# BEE_BOARD_TOP.net
KiCad netlist of a schematic drawn in Altium Designer
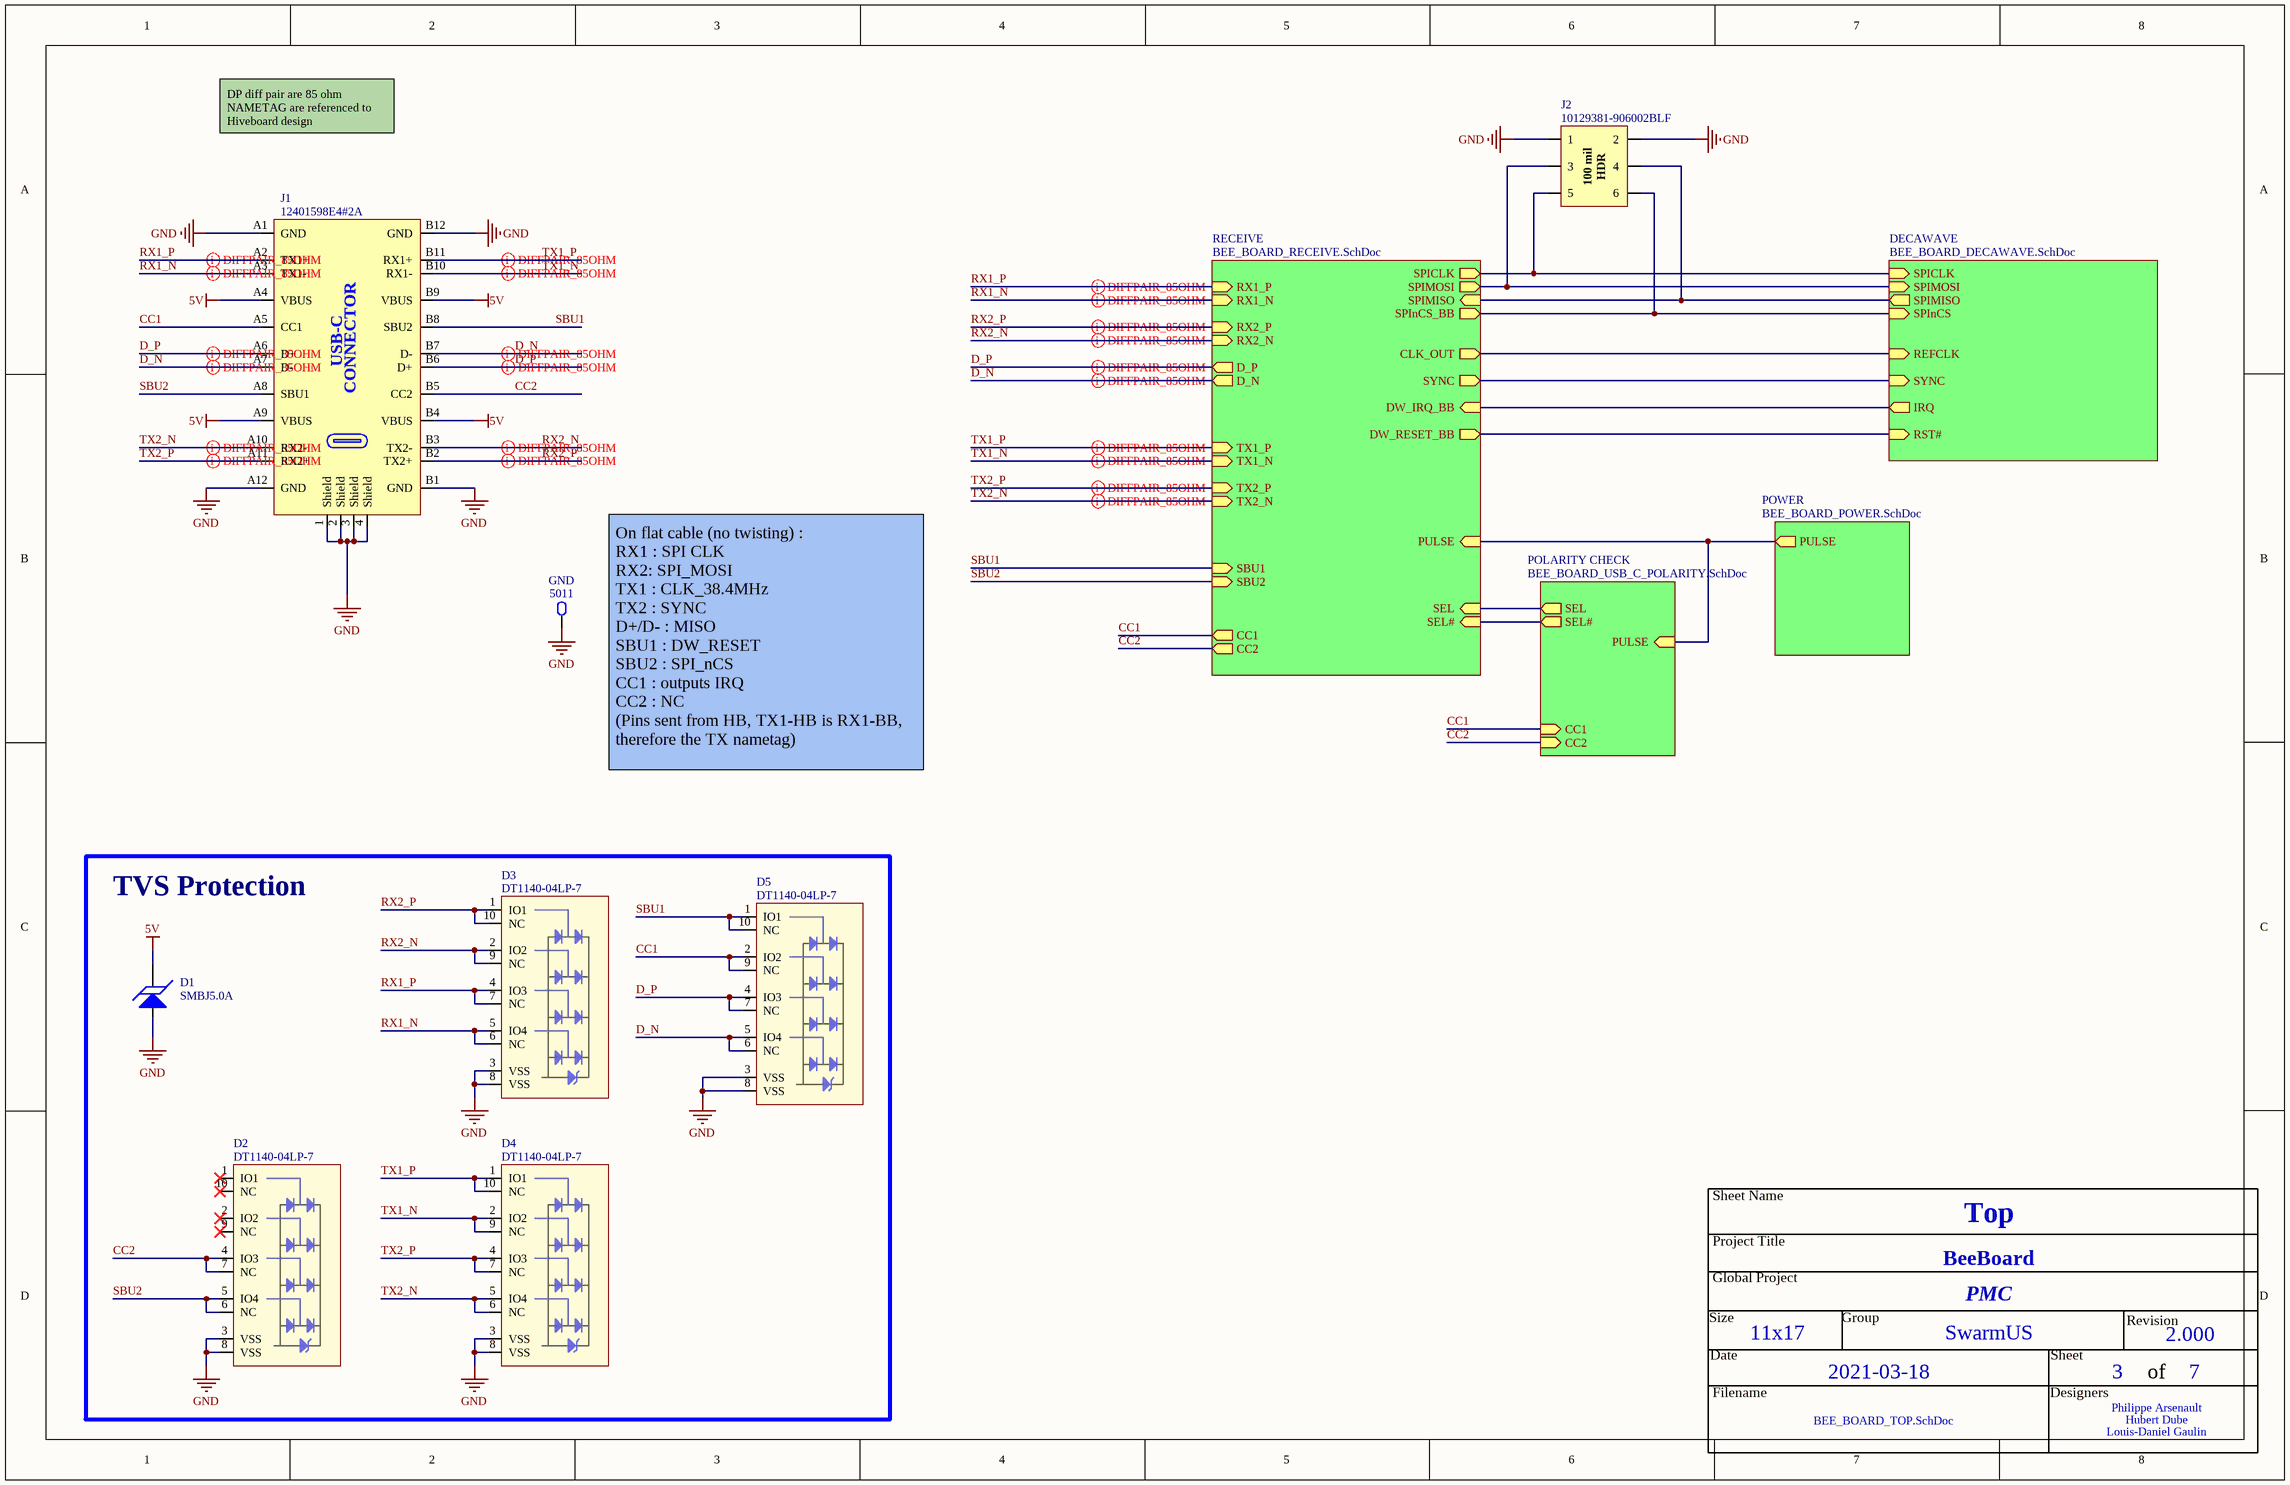
[diagram p0: BEE_BOARD_TOP.SchDoc]

(export (version "E")
  (design (tool "Eeschema 10.0.6"))
  (components
    (comp (ref "D1")
      (value "SMBJ5.0A")
      (footprint "TVS_PWR_SMBJ5.0CA")
      (description "TVS - BIDIR 5V 9.2V 600W - DO214AA")
      (fields
        (field (name "CREATEDBY/DATE") "Louis-Daniel Gaulin / 13-04-2021")
        (field (name "VERIFIEDBY") "Philippe Arsenault/2021-04-14")
      )
      (libsource (lib "SWARMUS_LIB") (part "TVS_PWR_SMBJ5.0A"))
    )
    (comp (ref "D2")
      (value "DT1140-04LP-7")
      (footprint "grams_master_lib_pcb:TVS_DATA_DT1140-04LP-7")
      (description "TVS - DIODE 5.5V 10V - 10-UFDFN")
      (fields
        (field (name "CREATEDBY/DATE") "Joël Lemay 2019-11-20")
        (field (name "VERIFIEDBY") "C.Paulin - 21/11/2019")
      )
      (libsource (lib "GRAMS_MASTER_LIB_SCH") (part "TVS_DATA_DT1140-04LP-7"))
    )
    (comp (ref "D3")
      (value "DT1140-04LP-7")
      (footprint "grams_master_lib_pcb:TVS_DATA_DT1140-04LP-7")
      (description "TVS - DIODE 5.5V 10V - 10-UFDFN")
      (fields
        (field (name "CREATEDBY/DATE") "Joël Lemay 2019-11-20")
        (field (name "VERIFIEDBY") "C.Paulin - 21/11/2019")
      )
      (libsource (lib "GRAMS_MASTER_LIB_SCH") (part "TVS_DATA_DT1140-04LP-7"))
    )
    (comp (ref "D4")
      (value "DT1140-04LP-7")
      (footprint "grams_master_lib_pcb:TVS_DATA_DT1140-04LP-7")
      (description "TVS - DIODE 5.5V 10V - 10-UFDFN")
      (fields
        (field (name "CREATEDBY/DATE") "Joël Lemay 2019-11-20")
        (field (name "VERIFIEDBY") "C.Paulin - 21/11/2019")
      )
      (libsource (lib "GRAMS_MASTER_LIB_SCH") (part "TVS_DATA_DT1140-04LP-7"))
    )
    (comp (ref "D5")
      (value "DT1140-04LP-7")
      (footprint "grams_master_lib_pcb:TVS_DATA_DT1140-04LP-7")
      (description "TVS - DIODE 5.5V 10V - 10-UFDFN")
      (fields
        (field (name "CREATEDBY/DATE") "Joël Lemay 2019-11-20")
        (field (name "VERIFIEDBY") "C.Paulin - 21/11/2019")
      )
      (libsource (lib "GRAMS_MASTER_LIB_SCH") (part "TVS_DATA_DT1140-04LP-7"))
    )
    (comp (ref "GND")
      (value "5011")
      (footprint "TPO_5011")
      (description "TPO - TEST POINT - TH")
      (fields
        (field (name "CREATEDBY/DATE") "Louis-Daniel Gauli / 02-11-2020")
        (field (name "VERIFIEDBY") "Philippe Arsenault/2020-11-06")
      )
      (libsource (lib "SWARMUS_LIB") (part "TPO_5011"))
    )
    (comp (ref "J1")
      (value "12401598E4#2A")
      (footprint "CON_USB_3.2_TypeC_12401598E4#2A")
      (description "CON_USB - USB 3.2 Gen 2 (USB 3.1 Gen 2, Superspeed + (USB 3.1)) 24 pos Receptacle - R/A")
      (fields
        (field (name "CREATEDBY/DATE") "Louis-Daniel Gaulin / 07-04-2021")
        (field (name "VERIFIEDBY") "Philippe Arsenault/2021-04-08")
      )
      (libsource (lib "SWARMUS_LIB") (part "CON_USB_3.2_TypeC_12401598E4#2A"))
    )
    (comp (ref "J2")
      (value "10129381-906002BLF")
      (footprint "CON_HDR_10129381-906002BLF")
      (description "CON - Header 6 positions 3x2  0.100\" - 6-TH")
      (fields (field (name "CREATEDBY/DATE") "Philippe Arsenault/2021-04-14"))
      (libsource (lib "SWARMUS_LIB") (part "CON_HDR_10129381-906002BLF"))
    )
  )
  (nets
    (net (code "1") (name "/CC1") (class "Default")
      (node (ref "D5") (pin "2") (pinfunction "IO2_2") (pintype "passive"))
      (node (ref "D5") (pin "9") (pinfunction "NC_9") (pintype "passive"))
      (node (ref "J1") (pin "A5") (pinfunction "CC1_A5") (pintype "passive"))
    )
    (net (code "2") (name "/CC2") (class "Default")
      (node (ref "D2") (pin "4") (pinfunction "IO3_4") (pintype "passive"))
      (node (ref "D2") (pin "7") (pinfunction "NC_7") (pintype "passive"))
      (node (ref "J1") (pin "B5") (pinfunction "CC2_B5") (pintype "passive"))
    )
    (net (code "5") (name "/D_N") (class "Default")
      (node (ref "D5") (pin "5") (pinfunction "IO4_5") (pintype "passive"))
      (node (ref "D5") (pin "6") (pinfunction "NC_6") (pintype "passive"))
      (node (ref "J1") (pin "A7") (pinfunction "D-_A7") (pintype "passive"))
      (node (ref "J1") (pin "B7") (pinfunction "D-_B7") (pintype "passive"))
    )
    (net (code "6") (name "/D_P") (class "Default")
      (node (ref "D5") (pin "4") (pinfunction "IO3_4") (pintype "passive"))
      (node (ref "D5") (pin "7") (pinfunction "NC_7") (pintype "passive"))
      (node (ref "J1") (pin "A6") (pinfunction "D+_A6") (pintype "passive"))
      (node (ref "J1") (pin "B6") (pinfunction "D+_B6") (pintype "passive"))
    )
    (net (code "9") (name "/RX1_N") (class "Default")
      (node (ref "D3") (pin "5") (pinfunction "IO4_5") (pintype "passive"))
      (node (ref "D3") (pin "6") (pinfunction "NC_6") (pintype "passive"))
      (node (ref "J1") (pin "A3") (pinfunction "TX1-_A3") (pintype "passive"))
    )
    (net (code "10") (name "/RX1_P") (class "Default")
      (node (ref "D3") (pin "4") (pinfunction "IO3_4") (pintype "passive"))
      (node (ref "D3") (pin "7") (pinfunction "NC_7") (pintype "passive"))
      (node (ref "J1") (pin "A2") (pinfunction "TX1+_A2") (pintype "passive"))
    )
    (net (code "11") (name "/RX2_N") (class "Default")
      (node (ref "D3") (pin "2") (pinfunction "IO2_2") (pintype "passive"))
      (node (ref "D3") (pin "9") (pinfunction "NC_9") (pintype "passive"))
      (node (ref "J1") (pin "B3") (pinfunction "TX2-_B3") (pintype "passive"))
    )
    (net (code "12") (name "/RX2_P") (class "Default")
      (node (ref "D3") (pin "1") (pinfunction "IO1_1") (pintype "passive"))
      (node (ref "D3") (pin "10") (pinfunction "NC_10") (pintype "passive"))
      (node (ref "J1") (pin "B2") (pinfunction "TX2+_B2") (pintype "passive"))
    )
    (net (code "13") (name "/SBU1") (class "Default")
      (node (ref "D5") (pin "1") (pinfunction "IO1_1") (pintype "passive"))
      (node (ref "D5") (pin "10") (pinfunction "NC_10") (pintype "passive"))
      (node (ref "J1") (pin "B8") (pinfunction "SBU2_B8") (pintype "passive"))
    )
    (net (code "14") (name "/SBU2") (class "Default")
      (node (ref "D2") (pin "5") (pinfunction "IO4_5") (pintype "passive"))
      (node (ref "D2") (pin "6") (pinfunction "NC_6") (pintype "passive"))
      (node (ref "J1") (pin "A8") (pinfunction "SBU1_A8") (pintype "passive"))
    )
    (net (code "17") (name "/SPICLK") (class "Default")
      (node (ref "J2") (pin "5") (pinfunction "5_5") (pintype "passive"))
    )
    (net (code "18") (name "/SPIMISO") (class "Default")
      (node (ref "J2") (pin "4") (pinfunction "4_4") (pintype "passive"))
    )
    (net (code "19") (name "/SPIMOSI") (class "Default")
      (node (ref "J2") (pin "3") (pinfunction "3_3") (pintype "passive"))
    )
    (net (code "20") (name "/SPInCS_BB") (class "Default")
      (node (ref "J2") (pin "6") (pinfunction "6_6") (pintype "passive"))
    )
    (net (code "22") (name "/TX1_N") (class "Default")
      (node (ref "D4") (pin "2") (pinfunction "IO2_2") (pintype "passive"))
      (node (ref "D4") (pin "9") (pinfunction "NC_9") (pintype "passive"))
      (node (ref "J1") (pin "B10") (pinfunction "RX1-_B10") (pintype "passive"))
    )
    (net (code "23") (name "/TX1_P") (class "Default")
      (node (ref "D4") (pin "1") (pinfunction "IO1_1") (pintype "passive"))
      (node (ref "D4") (pin "10") (pinfunction "NC_10") (pintype "passive"))
      (node (ref "J1") (pin "B11") (pinfunction "RX1+_B11") (pintype "passive"))
    )
    (net (code "24") (name "/TX2_N") (class "Default")
      (node (ref "D4") (pin "5") (pinfunction "IO4_5") (pintype "passive"))
      (node (ref "D4") (pin "6") (pinfunction "NC_6") (pintype "passive"))
      (node (ref "J1") (pin "A10") (pinfunction "RX2-_A10") (pintype "passive"))
    )
    (net (code "25") (name "/TX2_P") (class "Default")
      (node (ref "D4") (pin "4") (pinfunction "IO3_4") (pintype "passive"))
      (node (ref "D4") (pin "7") (pinfunction "NC_7") (pintype "passive"))
      (node (ref "J1") (pin "A11") (pinfunction "RX2+_A11") (pintype "passive"))
    )
    (net (code "26") (name "5V") (class "Default")
      (node (ref "D1") (pin "1") (pinfunction "1_1") (pintype "passive"))
      (node (ref "J1") (pin "A4") (pinfunction "VBUS_A4") (pintype "passive"))
      (node (ref "J1") (pin "A9") (pinfunction "VBUS_A9") (pintype "passive"))
      (node (ref "J1") (pin "B4") (pinfunction "VBUS_B4") (pintype "passive"))
      (node (ref "J1") (pin "B9") (pinfunction "VBUS_B9") (pintype "passive"))
    )
    (net (code "27") (name "GND") (class "Default")
      (node (ref "D1") (pin "2") (pinfunction "2_2") (pintype "passive"))
      (node (ref "D2") (pin "3") (pinfunction "VSS_3") (pintype "passive"))
      (node (ref "D2") (pin "8") (pinfunction "VSS_8") (pintype "passive"))
      (node (ref "D3") (pin "3") (pinfunction "VSS_3") (pintype "passive"))
      (node (ref "D3") (pin "8") (pinfunction "VSS_8") (pintype "passive"))
      (node (ref "D4") (pin "3") (pinfunction "VSS_3") (pintype "passive"))
      (node (ref "D4") (pin "8") (pinfunction "VSS_8") (pintype "passive"))
      (node (ref "D5") (pin "3") (pinfunction "VSS_3") (pintype "passive"))
      (node (ref "D5") (pin "8") (pinfunction "VSS_8") (pintype "passive"))
      (node (ref "GND") (pin "1") (pinfunction "1_1") (pintype "passive"))
      (node (ref "J1") (pin "1") (pinfunction "Shield_1") (pintype "passive"))
      (node (ref "J1") (pin "2") (pinfunction "Shield_2") (pintype "passive"))
      (node (ref "J1") (pin "3") (pinfunction "Shield_3") (pintype "passive"))
      (node (ref "J1") (pin "4") (pinfunction "Shield_4") (pintype "passive"))
      (node (ref "J1") (pin "A1") (pinfunction "GND_A1") (pintype "passive"))
      (node (ref "J1") (pin "A12") (pinfunction "GND_A12") (pintype "passive"))
      (node (ref "J1") (pin "B1") (pinfunction "GND_B1") (pintype "passive"))
      (node (ref "J1") (pin "B12") (pinfunction "GND_B12") (pintype "passive"))
      (node (ref "J2") (pin "1") (pinfunction "1_1") (pintype "passive"))
      (node (ref "J2") (pin "2") (pinfunction "2_2") (pintype "passive"))
    )
    (net (code "28") (name "unconnected-(D2-IO1-Pad1)") (class "Default")
      (node (ref "D2") (pin "1") (pinfunction "IO1_1") (pintype "passive+no_connect"))
    )
    (net (code "29") (name "unconnected-(D2-IO2-Pad2)") (class "Default")
      (node (ref "D2") (pin "2") (pinfunction "IO2_2") (pintype "passive+no_connect"))
    )
    (net (code "30") (name "unconnected-(D2-NC-Pad9)") (class "Default")
      (node (ref "D2") (pin "9") (pinfunction "NC_9") (pintype "passive+no_connect"))
    )
    (net (code "31") (name "unconnected-(D2-NC-Pad10)") (class "Default")
      (node (ref "D2") (pin "10") (pinfunction "NC_10") (pintype "passive+no_connect"))
    )
  )
)
